# Kingst51.net
KiCad netlist of a schematic drawn in Altium Designer
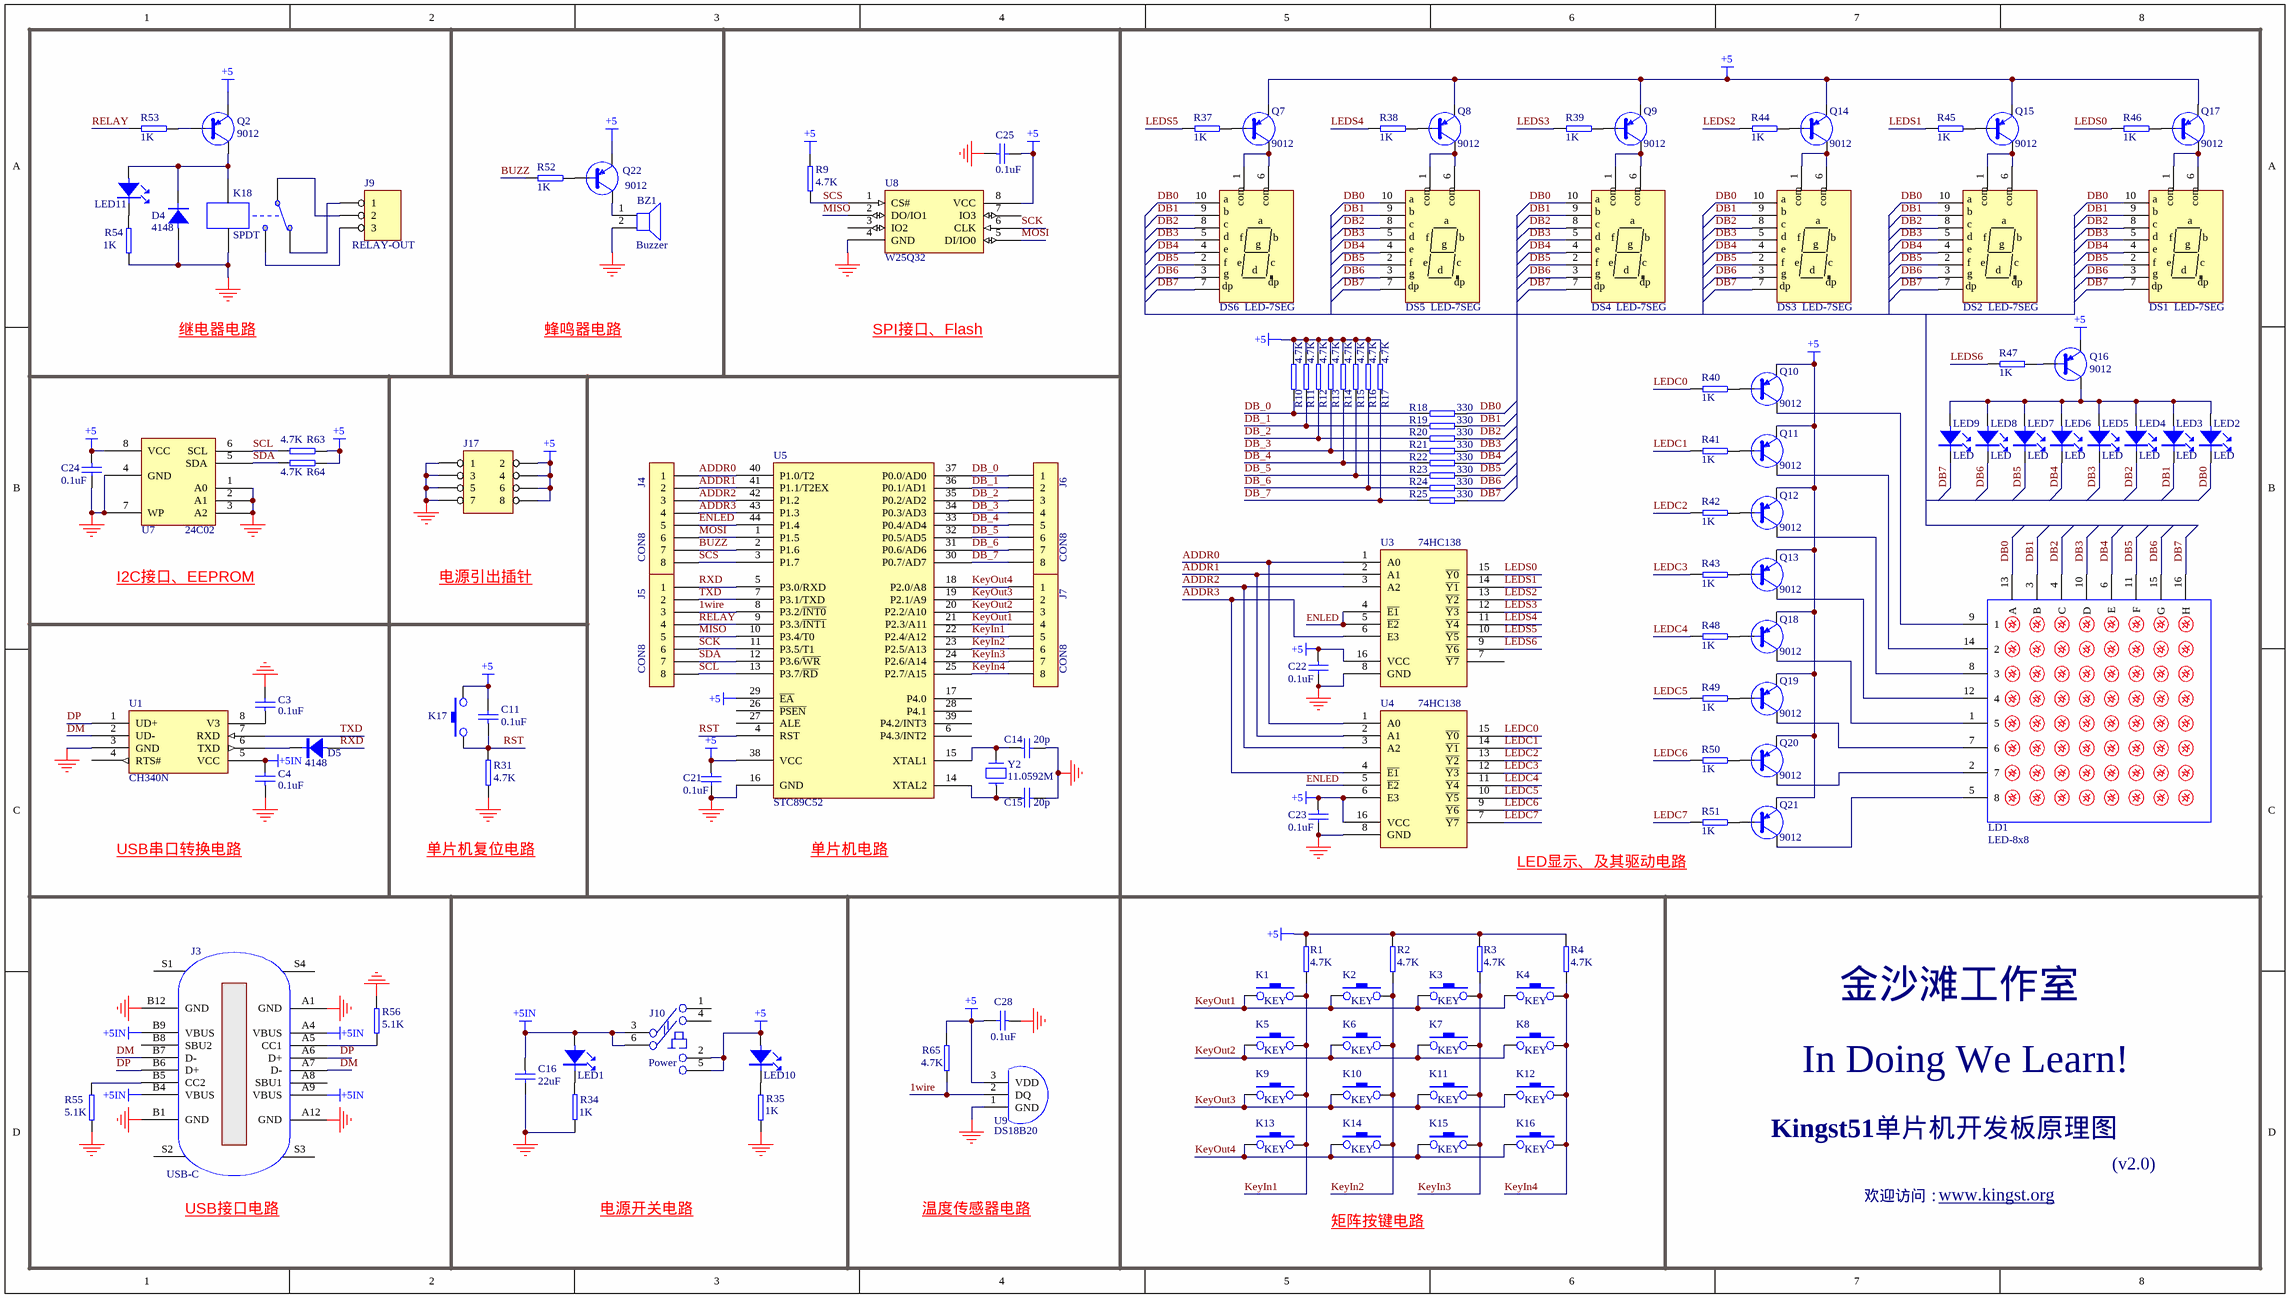
[diagram p0: Kingst51开发板原理图.SchDoc]

(export (version "E")
  (design (tool "Eeschema 10.0.6"))
  (components
    (comp (ref "BZ1") (value "Buzzer") (footprint "BUZZ-D12") (libsource (lib "*") (part "SPEAKER")))
    (comp (ref "C3") (value "0.1uF") (footprint "0603C") (libsource (lib "*") (part "CAP")))
    (comp (ref "C4") (value "0.1uF") (footprint "0603C") (libsource (lib "*") (part "CAP")))
    (comp (ref "C11") (value "0.1uF") (footprint "0603C") (libsource (lib "*") (part "CAP")))
    (comp (ref "C14") (value "20p") (footprint "0603C") (libsource (lib "*") (part "CAP")))
    (comp (ref "C15") (value "20p") (footprint "0603C") (libsource (lib "*") (part "CAP")))
    (comp (ref "C16") (value "22uF") (footprint "0805C") (libsource (lib "*") (part "CAP")))
    (comp (ref "C21") (value "0.1uF") (footprint "0603C") (libsource (lib "*") (part "CAP")))
    (comp (ref "C22") (value "0.1uF") (footprint "0603C") (libsource (lib "*") (part "CAP")))
    (comp (ref "C23") (value "0.1uF") (footprint "0603C") (libsource (lib "*") (part "CAP")))
    (comp (ref "C24") (value "0.1uF") (footprint "0603C") (libsource (lib "*") (part "CAP")))
    (comp (ref "C25") (value "0.1uF") (footprint "0603C") (libsource (lib "*") (part "CAP")))
    (comp (ref "C28") (value "0.1uF") (footprint "0603C") (libsource (lib "*") (part "CAP")))
    (comp (ref "D4")
      (value "4148")
      (footprint "SOD-123")
      (description "DIODE")
      (libsource (lib "schOthers") (part "DIODE"))
    )
    (comp (ref "D5")
      (value "4148")
      (footprint "SOD-123")
      (description "DIODE")
      (libsource (lib "schOthers") (part "DIODE"))
    )
    (comp (ref "DS1")
      (value "LED-7SEG")
      (footprint "LED-C7")
      (description "Seven-Segment Display, Right Hand Decimal")
      (libsource (lib "*") (part "LED-7SEG"))
    )
    (comp (ref "DS2")
      (value "LED-7SEG")
      (footprint "LED-C7")
      (description "Seven-Segment Display, Right Hand Decimal")
      (libsource (lib "*") (part "LED-7SEG"))
    )
    (comp (ref "DS3")
      (value "LED-7SEG")
      (footprint "LED-C7")
      (description "Seven-Segment Display, Right Hand Decimal")
      (libsource (lib "*") (part "LED-7SEG"))
    )
    (comp (ref "DS4")
      (value "LED-7SEG")
      (footprint "LED-C7")
      (description "Seven-Segment Display, Right Hand Decimal")
      (libsource (lib "*") (part "LED-7SEG"))
    )
    (comp (ref "DS5")
      (value "LED-7SEG")
      (footprint "LED-C7")
      (description "Seven-Segment Display, Right Hand Decimal")
      (libsource (lib "*") (part "LED-7SEG"))
    )
    (comp (ref "DS6")
      (value "LED-7SEG")
      (footprint "LED-C7")
      (description "Seven-Segment Display, Right Hand Decimal")
      (libsource (lib "*") (part "LED-7SEG"))
    )
    (comp (ref "J3")
      (value "USB-C")
      (footprint "USB-C-16P")
      (description "USB Type-C 16P 型插座")
      (libsource (lib "schOthers") (part "USB-C-16P"))
    )
    (comp (ref "J4")
      (value "CON8")
      (footprint "SIP8")
      (description "Connector")
      (libsource (lib "") (part "CON8_1"))
    )
    (comp (ref "J5")
      (value "CON8")
      (footprint "SIP8")
      (description "Connector")
      (libsource (lib "") (part "CON8_1"))
    )
    (comp (ref "J6")
      (value "CON8")
      (footprint "SIP8")
      (description "Connector")
      (libsource (lib "*") (part "CON8"))
    )
    (comp (ref "J7")
      (value "CON8")
      (footprint "SIP8")
      (description "Connector")
      (libsource (lib "*") (part "CON8"))
    )
    (comp (ref "J9")
      (value "RELAY-OUT")
      (footprint "P5.08-3P")
      (description "Connector 3p")
      (libsource (lib "schOthers") (part "CON3"))
    )
    (comp (ref "J10")
      (value "Power")
      (description "Self-locking button")
      (libsource (lib "schOthers") (part "KEY-SL"))
    )
    (comp (ref "J17")
      (value "CON4X2")
      (footprint "IDC4X2-M")
      (description "Connector 4*2p")
      (libsource (lib "schOthers") (part "CON4X2"))
    )
    (comp (ref "K1") (value "KEY") (footprint "KEY-6X6") (libsource (lib "*") (part "KEY")))
    (comp (ref "K2") (value "KEY") (footprint "KEY-6X6") (libsource (lib "*") (part "KEY")))
    (comp (ref "K3") (value "KEY") (footprint "KEY-6X6") (libsource (lib "*") (part "KEY")))
    (comp (ref "K4") (value "KEY") (footprint "KEY-6X6") (libsource (lib "*") (part "KEY")))
    (comp (ref "K5") (value "KEY") (footprint "KEY-6X6") (libsource (lib "*") (part "KEY")))
    (comp (ref "K6") (value "KEY") (footprint "KEY-6X6") (libsource (lib "*") (part "KEY")))
    (comp (ref "K7") (value "KEY") (footprint "KEY-6X6") (libsource (lib "*") (part "KEY")))
    (comp (ref "K8") (value "KEY") (footprint "KEY-6X6") (libsource (lib "*") (part "KEY")))
    (comp (ref "K9") (value "KEY") (footprint "KEY-6X6") (libsource (lib "*") (part "KEY")))
    (comp (ref "K10") (value "KEY") (footprint "KEY-6X6") (libsource (lib "*") (part "KEY")))
    (comp (ref "K11") (value "KEY") (footprint "KEY-6X6") (libsource (lib "*") (part "KEY")))
    (comp (ref "K12") (value "KEY") (footprint "KEY-6X6") (libsource (lib "*") (part "KEY")))
    (comp (ref "K13") (value "KEY") (footprint "KEY-6X6") (libsource (lib "*") (part "KEY")))
    (comp (ref "K14") (value "KEY") (footprint "KEY-6X6") (libsource (lib "*") (part "KEY")))
    (comp (ref "K15") (value "KEY") (footprint "KEY-6X6") (libsource (lib "*") (part "KEY")))
    (comp (ref "K16") (value "KEY") (footprint "KEY-6X6") (libsource (lib "*") (part "KEY")))
    (comp (ref "K17") (value "RESET") (footprint "KEY-6X6") (libsource (lib "*") (part "KEY")))
    (comp (ref "K18")
      (value "SPDT")
      (footprint "RELAY-SPDT")
      (libsource (lib "schOthers") (part "RELAY-SPDT"))
    )
    (comp (ref "LD1") (value "LED-8x8") (footprint "LED-8*8") (libsource (lib "*") (part "LED-8*8")))
    (comp (ref "LED1") (value "LED") (footprint "0805LD") (libsource (lib "*") (part "LED")))
    (comp (ref "LED2") (value "LED") (footprint "0805LD") (libsource (lib "*") (part "LED")))
    (comp (ref "LED3") (value "LED") (footprint "0805LD") (libsource (lib "*") (part "LED")))
    (comp (ref "LED4") (value "LED") (footprint "0805LD") (libsource (lib "*") (part "LED")))
    (comp (ref "LED5") (value "LED") (footprint "0805LD") (libsource (lib "*") (part "LED")))
    (comp (ref "LED6") (value "LED") (footprint "0805LD") (libsource (lib "*") (part "LED")))
    (comp (ref "LED7") (value "LED") (footprint "0805LD") (libsource (lib "*") (part "LED")))
    (comp (ref "LED8") (value "LED") (footprint "0805LD") (libsource (lib "*") (part "LED")))
    (comp (ref "LED9") (value "LED") (footprint "0805LD") (libsource (lib "*") (part "LED")))
    (comp (ref "LED10") (value "LED") (footprint "0805LD") (libsource (lib "*") (part "LED")))
    (comp (ref "LED11") (value "LED") (footprint "0805LD") (libsource (lib "*") (part "LED")))
    (comp (ref "Q2") (value "9012") (footprint "SOT-23-Q") (libsource (lib "*") (part "2N-PNP")))
    (comp (ref "Q7") (value "9012") (footprint "SOT-23-Q") (libsource (lib "*") (part "2N-PNP")))
    (comp (ref "Q8") (value "9012") (footprint "SOT-23-Q") (libsource (lib "*") (part "2N-PNP")))
    (comp (ref "Q9") (value "9012") (footprint "SOT-23-Q") (libsource (lib "*") (part "2N-PNP")))
    (comp (ref "Q10") (value "9012") (footprint "SOT-23-Q") (libsource (lib "*") (part "2N-PNP")))
    (comp (ref "Q11") (value "9012") (footprint "SOT-23-Q") (libsource (lib "*") (part "2N-PNP")))
    (comp (ref "Q12") (value "9012") (footprint "SOT-23-Q") (libsource (lib "*") (part "2N-PNP")))
    (comp (ref "Q13") (value "9012") (footprint "SOT-23-Q") (libsource (lib "*") (part "2N-PNP")))
    (comp (ref "Q14") (value "9012") (footprint "SOT-23-Q") (libsource (lib "*") (part "2N-PNP")))
    (comp (ref "Q15") (value "9012") (footprint "SOT-23-Q") (libsource (lib "*") (part "2N-PNP")))
    (comp (ref "Q16") (value "9012") (footprint "SOT-23-Q") (libsource (lib "*") (part "2N-PNP")))
    (comp (ref "Q17") (value "9012") (footprint "SOT-23-Q") (libsource (lib "*") (part "2N-PNP")))
    (comp (ref "Q18") (value "9012") (footprint "SOT-23-Q") (libsource (lib "*") (part "2N-PNP")))
    (comp (ref "Q19") (value "9012") (footprint "SOT-23-Q") (libsource (lib "*") (part "2N-PNP")))
    (comp (ref "Q20") (value "9012") (footprint "SOT-23-Q") (libsource (lib "*") (part "2N-PNP")))
    (comp (ref "Q21") (value "9012") (footprint "SOT-23-Q") (libsource (lib "*") (part "2N-PNP")))
    (comp (ref "Q22") (value "9012") (footprint "SOT-23-Q") (libsource (lib "*") (part "2N-PNP")))
    (comp (ref "R1") (value "4.7K") (footprint "0603R") (libsource (lib "*") (part "RES2")))
    (comp (ref "R2") (value "4.7K") (footprint "0603R") (libsource (lib "*") (part "RES2")))
    (comp (ref "R3") (value "4.7K") (footprint "0603R") (libsource (lib "*") (part "RES2")))
    (comp (ref "R4") (value "4.7K") (footprint "0603R") (libsource (lib "*") (part "RES2")))
    (comp (ref "R9") (value "4.7K") (footprint "0603R") (libsource (lib "*") (part "RES2")))
    (comp (ref "R10") (value "4.7K") (footprint "0603R") (libsource (lib "*") (part "RES2")))
    (comp (ref "R11") (value "4.7K") (footprint "0603R") (libsource (lib "*") (part "RES2")))
    (comp (ref "R12") (value "4.7K") (footprint "0603R") (libsource (lib "*") (part "RES2")))
    (comp (ref "R13") (value "4.7K") (footprint "0603R") (libsource (lib "*") (part "RES2")))
    (comp (ref "R14") (value "4.7K") (footprint "0603R") (libsource (lib "*") (part "RES2")))
    (comp (ref "R15") (value "4.7K") (footprint "0603R") (libsource (lib "*") (part "RES2")))
    (comp (ref "R16") (value "4.7K") (footprint "0603R") (libsource (lib "*") (part "RES2")))
    (comp (ref "R17") (value "4.7K") (footprint "0603R") (libsource (lib "*") (part "RES2")))
    (comp (ref "R18") (value "330") (footprint "0603R") (libsource (lib "*") (part "RES2")))
    (comp (ref "R19") (value "330") (footprint "0603R") (libsource (lib "*") (part "RES2")))
    (comp (ref "R20") (value "330") (footprint "0603R") (libsource (lib "*") (part "RES2")))
    (comp (ref "R21") (value "330") (footprint "0603R") (libsource (lib "*") (part "RES2")))
    (comp (ref "R22") (value "330") (footprint "0603R") (libsource (lib "*") (part "RES2")))
    (comp (ref "R23") (value "330") (footprint "0603R") (libsource (lib "*") (part "RES2")))
    (comp (ref "R24") (value "330") (footprint "0603R") (libsource (lib "*") (part "RES2")))
    (comp (ref "R25") (value "330") (footprint "0603R") (libsource (lib "*") (part "RES2")))
    (comp (ref "R31") (value "4.7K") (footprint "0603R") (libsource (lib "*") (part "RES2")))
    (comp (ref "R34") (value "1K") (footprint "0603R") (libsource (lib "*") (part "RES2")))
    (comp (ref "R35") (value "1K") (footprint "0603R") (libsource (lib "*") (part "RES2")))
    (comp (ref "R37") (value "1K") (footprint "0603R") (libsource (lib "*") (part "RES2")))
    (comp (ref "R38") (value "1K") (footprint "0603R") (libsource (lib "*") (part "RES2")))
    (comp (ref "R39") (value "1K") (footprint "0603R") (libsource (lib "*") (part "RES2")))
    (comp (ref "R40") (value "1K") (footprint "0603R") (libsource (lib "*") (part "RES2")))
    (comp (ref "R41") (value "1K") (footprint "0603R") (libsource (lib "*") (part "RES2")))
    (comp (ref "R42") (value "1K") (footprint "0603R") (libsource (lib "*") (part "RES2")))
    (comp (ref "R43") (value "1K") (footprint "0603R") (libsource (lib "*") (part "RES2")))
    (comp (ref "R44") (value "1K") (footprint "0603R") (libsource (lib "*") (part "RES2")))
    (comp (ref "R45") (value "1K") (footprint "0603R") (libsource (lib "*") (part "RES2")))
    (comp (ref "R46") (value "1K") (footprint "0603R") (libsource (lib "*") (part "RES2")))
    (comp (ref "R47") (value "1K") (footprint "0603R") (libsource (lib "*") (part "RES2")))
    (comp (ref "R48") (value "1K") (footprint "0603R") (libsource (lib "*") (part "RES2")))
    (comp (ref "R49") (value "1K") (footprint "0603R") (libsource (lib "*") (part "RES2")))
    (comp (ref "R50") (value "1K") (footprint "0603R") (libsource (lib "*") (part "RES2")))
    (comp (ref "R51") (value "1K") (footprint "0603R") (libsource (lib "*") (part "RES2")))
    (comp (ref "R52") (value "1K") (footprint "0603R") (libsource (lib "*") (part "RES2")))
    (comp (ref "R53") (value "1K") (footprint "0603R") (libsource (lib "*") (part "RES2")))
    (comp (ref "R54") (value "1K") (footprint "0603R") (libsource (lib "*") (part "RES2")))
    (comp (ref "R55") (value "5.1K") (footprint "0603R") (libsource (lib "*") (part "RES2")))
    (comp (ref "R56") (value "5.1K") (footprint "0603R") (libsource (lib "*") (part "RES2")))
    (comp (ref "R63") (value "4.7K") (footprint "0603R") (libsource (lib "*") (part "RES2")))
    (comp (ref "R64") (value "4.7K") (footprint "0603R") (libsource (lib "*") (part "RES2")))
    (comp (ref "R65") (value "4.7K") (footprint "0603R") (libsource (lib "*") (part "RES2")))
    (comp (ref "U1")
      (value "CH340N")
      (footprint "SOP-8_3.9")
      (description "USB to UART Bridge Controller")
      (libsource (lib "schChips") (part "CH340N"))
    )
    (comp (ref "U3") (value "74HC138") (footprint "SOP-16_3.9") (libsource (lib "*") (part "74XX138")))
    (comp (ref "U4") (value "74HC138") (footprint "SOP-16_3.9") (libsource (lib "*") (part "74XX138")))
    (comp (ref "U5")
      (value "STC89C52")
      (footprint "LQFP44_0.8")
      (description "STC89C52 LQFP44")
      (libsource (lib "schProcessor") (part "STC89C52-44P"))
    )
    (comp (ref "U7") (value "24C02") (footprint "SOP-8_3.9") (libsource (lib "*") (part "24C01")))
    (comp (ref "U8")
      (value "W25Q32")
      (footprint "SOP-8_5.3")
      (description "SPI Serial Flash")
      (libsource (lib "schChips") (part "W25Q128"))
    )
    (comp (ref "U9") (value "DS18B20") (footprint "TO-92") (libsource (lib "*") (part "DS18B20")))
    (comp (ref "Y2")
      (value "11.0592M")
      (footprint "SMD-3225-4P")
      (description "Crystal")
      (libsource (lib "schOthers") (part "CRYSTAL"))
    )
  )
  (nets
    (net (code "1") (name "+5") (class "Default")
      (node (ref "C11") (pin "2") (pinfunction "2_2") (pintype "passive"))
      (node (ref "C21") (pin "1") (pinfunction "1_1") (pintype "passive"))
      (node (ref "C22") (pin "1") (pinfunction "1_1") (pintype "passive"))
      (node (ref "C23") (pin "1") (pinfunction "1_1") (pintype "passive"))
      (node (ref "C24") (pin "1") (pinfunction "1_1") (pintype "passive"))
      (node (ref "C25") (pin "2") (pinfunction "2_2") (pintype "passive"))
      (node (ref "C28") (pin "2") (pinfunction "2_2") (pintype "passive"))
      (node (ref "J10") (pin "2") (pinfunction "2_2") (pintype "passive"))
      (node (ref "J10") (pin "5") (pinfunction "5_5") (pintype "passive"))
      (node (ref "J17") (pin "2") (pinfunction "2_2") (pintype "passive"))
      (node (ref "J17") (pin "4") (pinfunction "4_4") (pintype "passive"))
      (node (ref "J17") (pin "6") (pinfunction "6_6") (pintype "passive"))
      (node (ref "J17") (pin "8") (pinfunction "8_8") (pintype "passive"))
      (node (ref "K17") (pin "2") (pinfunction "2_2") (pintype "passive"))
      (node (ref "LED10") (pin "A") (pinfunction "1_A") (pintype "passive"))
      (node (ref "Q10") (pin "E") (pinfunction "E_E") (pintype "passive"))
      (node (ref "Q11") (pin "E") (pinfunction "E_E") (pintype "passive"))
      (node (ref "Q12") (pin "E") (pinfunction "E_E") (pintype "passive"))
      (node (ref "Q13") (pin "E") (pinfunction "E_E") (pintype "passive"))
      (node (ref "Q14") (pin "E") (pinfunction "E_E") (pintype "passive"))
      (node (ref "Q15") (pin "E") (pinfunction "E_E") (pintype "passive"))
      (node (ref "Q16") (pin "E") (pinfunction "E_E") (pintype "passive"))
      (node (ref "Q17") (pin "E") (pinfunction "E_E") (pintype "passive"))
      (node (ref "Q18") (pin "E") (pinfunction "E_E") (pintype "passive"))
      (node (ref "Q19") (pin "E") (pinfunction "E_E") (pintype "passive"))
      (node (ref "Q2") (pin "E") (pinfunction "E_E") (pintype "passive"))
      (node (ref "Q20") (pin "E") (pinfunction "E_E") (pintype "passive"))
      (node (ref "Q21") (pin "E") (pinfunction "E_E") (pintype "passive"))
      (node (ref "Q22") (pin "E") (pinfunction "E_E") (pintype "passive"))
      (node (ref "Q7") (pin "E") (pinfunction "E_E") (pintype "passive"))
      (node (ref "Q8") (pin "E") (pinfunction "E_E") (pintype "passive"))
      (node (ref "Q9") (pin "E") (pinfunction "E_E") (pintype "passive"))
      (node (ref "R1") (pin "2") (pinfunction "2_2") (pintype "passive"))
      (node (ref "R10") (pin "2") (pinfunction "2_2") (pintype "passive"))
      (node (ref "R11") (pin "2") (pinfunction "2_2") (pintype "passive"))
      (node (ref "R12") (pin "2") (pinfunction "2_2") (pintype "passive"))
      (node (ref "R13") (pin "2") (pinfunction "2_2") (pintype "passive"))
      (node (ref "R14") (pin "2") (pinfunction "2_2") (pintype "passive"))
      (node (ref "R15") (pin "2") (pinfunction "2_2") (pintype "passive"))
      (node (ref "R16") (pin "2") (pinfunction "2_2") (pintype "passive"))
      (node (ref "R17") (pin "2") (pinfunction "2_2") (pintype "passive"))
      (node (ref "R2") (pin "2") (pinfunction "2_2") (pintype "passive"))
      (node (ref "R3") (pin "2") (pinfunction "2_2") (pintype "passive"))
      (node (ref "R4") (pin "2") (pinfunction "2_2") (pintype "passive"))
      (node (ref "R63") (pin "2") (pinfunction "2_2") (pintype "passive"))
      (node (ref "R64") (pin "2") (pinfunction "2_2") (pintype "passive"))
      (node (ref "R65") (pin "2") (pinfunction "2_2") (pintype "passive"))
      (node (ref "R9") (pin "2") (pinfunction "2_2") (pintype "passive"))
      (node (ref "U3") (pin "16") (pinfunction "VCC_16") (pintype "passive"))
      (node (ref "U4") (pin "16") (pinfunction "VCC_16") (pintype "passive"))
      (node (ref "U4") (pin "6") (pinfunction "E3_6") (pintype "passive"))
      (node (ref "U5") (pin "29") (pinfunction "~{EA}_29") (pintype "passive"))
      (node (ref "U5") (pin "38") (pinfunction "VCC_38") (pintype "passive"))
      (node (ref "U7") (pin "8") (pinfunction "VCC_8") (pintype "passive"))
      (node (ref "U8") (pin "8") (pinfunction "VCC_8") (pintype "power_in"))
      (node (ref "U9") (pin "3") (pinfunction "VDD_3") (pintype "passive"))
    )
    (net (code "2") (name "+5IN") (class "Default")
      (node (ref "C16") (pin "1") (pinfunction "1_1") (pintype "passive"))
      (node (ref "C4") (pin "2") (pinfunction "2_2") (pintype "passive"))
      (node (ref "J10") (pin "3") (pinfunction "3_3") (pintype "passive"))
      (node (ref "J10") (pin "6") (pinfunction "6_6") (pintype "passive"))
      (node (ref "J3") (pin "A4") (pinfunction "VBUS_A4") (pintype "passive"))
      (node (ref "J3") (pin "A9") (pinfunction "VBUS_A9") (pintype "passive"))
      (node (ref "J3") (pin "B4") (pinfunction "VBUS_B4") (pintype "passive"))
      (node (ref "J3") (pin "B9") (pinfunction "VBUS_B9") (pintype "passive"))
      (node (ref "LED1") (pin "A") (pinfunction "1_A") (pintype "passive"))
      (node (ref "U1") (pin "5") (pinfunction "VCC_5") (pintype "passive"))
    )
    (net (code "3") (name "/1wire") (class "Default")
      (node (ref "J5") (pin "3") (pinfunction "3_3") (pintype "passive"))
      (node (ref "R65") (pin "1") (pinfunction "1_1") (pintype "passive"))
      (node (ref "U5") (pin "8") (pinfunction "P3.2/~{INT0}_8") (pintype "passive"))
      (node (ref "U9") (pin "2") (pinfunction "DQ_2") (pintype "passive"))
    )
    (net (code "4") (name "/ADDR0") (class "Default")
      (node (ref "J4") (pin "1") (pinfunction "1_1") (pintype "passive"))
      (node (ref "U3") (pin "1") (pinfunction "A0_1") (pintype "passive"))
      (node (ref "U4") (pin "1") (pinfunction "A0_1") (pintype "passive"))
      (node (ref "U5") (pin "40") (pinfunction "P1.0/T2_40") (pintype "passive"))
    )
    (net (code "5") (name "/ADDR1") (class "Default")
      (node (ref "J4") (pin "2") (pinfunction "2_2") (pintype "passive"))
      (node (ref "U3") (pin "2") (pinfunction "A1_2") (pintype "passive"))
      (node (ref "U4") (pin "2") (pinfunction "A1_2") (pintype "passive"))
      (node (ref "U5") (pin "41") (pinfunction "P1.1/T2EX_41") (pintype "passive"))
    )
    (net (code "6") (name "/ADDR2") (class "Default")
      (node (ref "J4") (pin "3") (pinfunction "3_3") (pintype "passive"))
      (node (ref "U3") (pin "3") (pinfunction "A2_3") (pintype "passive"))
      (node (ref "U4") (pin "3") (pinfunction "A2_3") (pintype "passive"))
      (node (ref "U5") (pin "42") (pinfunction "P1.2_42") (pintype "passive"))
    )
    (net (code "7") (name "/ADDR3") (class "Default")
      (node (ref "J4") (pin "4") (pinfunction "4_4") (pintype "passive"))
      (node (ref "U3") (pin "6") (pinfunction "E3_6") (pintype "passive"))
      (node (ref "U4") (pin "4") (pinfunction "~{E1}_4") (pintype "passive"))
      (node (ref "U5") (pin "43") (pinfunction "P1.3_43") (pintype "passive"))
    )
    (net (code "8") (name "/BUZZ") (class "Default")
      (node (ref "J4") (pin "7") (pinfunction "7_7") (pintype "passive"))
      (node (ref "R52") (pin "1") (pinfunction "1_1") (pintype "passive"))
      (node (ref "U5") (pin "2") (pinfunction "P1.6_2") (pintype "passive"))
    )
    (net (code "9") (name "/DB0") (class "Default")
      (node (ref "DS1") (pin "10") (pinfunction "a_10") (pintype "passive"))
      (node (ref "DS2") (pin "10") (pinfunction "a_10") (pintype "passive"))
      (node (ref "DS3") (pin "10") (pinfunction "a_10") (pintype "passive"))
      (node (ref "DS4") (pin "10") (pinfunction "a_10") (pintype "passive"))
      (node (ref "DS5") (pin "10") (pinfunction "a_10") (pintype "passive"))
      (node (ref "DS6") (pin "10") (pinfunction "a_10") (pintype "passive"))
      (node (ref "LD1") (pin "13") (pinfunction "A_13") (pintype "passive"))
      (node (ref "LED2") (pin "K") (pinfunction "2_K") (pintype "passive"))
      (node (ref "R18") (pin "1") (pinfunction "1_1") (pintype "passive"))
    )
    (net (code "10") (name "/DB1") (class "Default")
      (node (ref "DS1") (pin "9") (pinfunction "b_9") (pintype "passive"))
      (node (ref "DS2") (pin "9") (pinfunction "b_9") (pintype "passive"))
      (node (ref "DS3") (pin "9") (pinfunction "b_9") (pintype "passive"))
      (node (ref "DS4") (pin "9") (pinfunction "b_9") (pintype "passive"))
      (node (ref "DS5") (pin "9") (pinfunction "b_9") (pintype "passive"))
      (node (ref "DS6") (pin "9") (pinfunction "b_9") (pintype "passive"))
      (node (ref "LD1") (pin "3") (pinfunction "B_3") (pintype "passive"))
      (node (ref "LED3") (pin "K") (pinfunction "2_K") (pintype "passive"))
      (node (ref "R19") (pin "1") (pinfunction "1_1") (pintype "passive"))
    )
    (net (code "11") (name "/DB2") (class "Default")
      (node (ref "DS1") (pin "8") (pinfunction "c_8") (pintype "passive"))
      (node (ref "DS2") (pin "8") (pinfunction "c_8") (pintype "passive"))
      (node (ref "DS3") (pin "8") (pinfunction "c_8") (pintype "passive"))
      (node (ref "DS4") (pin "8") (pinfunction "c_8") (pintype "passive"))
      (node (ref "DS5") (pin "8") (pinfunction "c_8") (pintype "passive"))
      (node (ref "DS6") (pin "8") (pinfunction "c_8") (pintype "passive"))
      (node (ref "LD1") (pin "4") (pinfunction "C_4") (pintype "passive"))
      (node (ref "LED4") (pin "K") (pinfunction "2_K") (pintype "passive"))
      (node (ref "R20") (pin "1") (pinfunction "1_1") (pintype "passive"))
    )
    (net (code "12") (name "/DB3") (class "Default")
      (node (ref "DS1") (pin "5") (pinfunction "d_5") (pintype "passive"))
      (node (ref "DS2") (pin "5") (pinfunction "d_5") (pintype "passive"))
      (node (ref "DS3") (pin "5") (pinfunction "d_5") (pintype "passive"))
      (node (ref "DS4") (pin "5") (pinfunction "d_5") (pintype "passive"))
      (node (ref "DS5") (pin "5") (pinfunction "d_5") (pintype "passive"))
      (node (ref "DS6") (pin "5") (pinfunction "d_5") (pintype "passive"))
      (node (ref "LD1") (pin "10") (pinfunction "D_10") (pintype "passive"))
      (node (ref "LED5") (pin "K") (pinfunction "2_K") (pintype "passive"))
      (node (ref "R21") (pin "1") (pinfunction "1_1") (pintype "passive"))
    )
    (net (code "13") (name "/DB4") (class "Default")
      (node (ref "DS1") (pin "4") (pinfunction "e_4") (pintype "passive"))
      (node (ref "DS2") (pin "4") (pinfunction "e_4") (pintype "passive"))
      (node (ref "DS3") (pin "4") (pinfunction "e_4") (pintype "passive"))
      (node (ref "DS4") (pin "4") (pinfunction "e_4") (pintype "passive"))
      (node (ref "DS5") (pin "4") (pinfunction "e_4") (pintype "passive"))
      (node (ref "DS6") (pin "4") (pinfunction "e_4") (pintype "passive"))
      (node (ref "LD1") (pin "6") (pinfunction "E_6") (pintype "passive"))
      (node (ref "LED6") (pin "K") (pinfunction "2_K") (pintype "passive"))
      (node (ref "R22") (pin "1") (pinfunction "1_1") (pintype "passive"))
    )
    (net (code "14") (name "/DB5") (class "Default")
      (node (ref "DS1") (pin "2") (pinfunction "f_2") (pintype "passive"))
      (node (ref "DS2") (pin "2") (pinfunction "f_2") (pintype "passive"))
      (node (ref "DS3") (pin "2") (pinfunction "f_2") (pintype "passive"))
      (node (ref "DS4") (pin "2") (pinfunction "f_2") (pintype "passive"))
      (node (ref "DS5") (pin "2") (pinfunction "f_2") (pintype "passive"))
      (node (ref "DS6") (pin "2") (pinfunction "f_2") (pintype "passive"))
      (node (ref "LD1") (pin "11") (pinfunction "F_11") (pintype "passive"))
      (node (ref "LED7") (pin "K") (pinfunction "2_K") (pintype "passive"))
      (node (ref "R23") (pin "1") (pinfunction "1_1") (pintype "passive"))
    )
    (net (code "15") (name "/DB6") (class "Default")
      (node (ref "DS1") (pin "3") (pinfunction "g_3") (pintype "passive"))
      (node (ref "DS2") (pin "3") (pinfunction "g_3") (pintype "passive"))
      (node (ref "DS3") (pin "3") (pinfunction "g_3") (pintype "passive"))
      (node (ref "DS4") (pin "3") (pinfunction "g_3") (pintype "passive"))
      (node (ref "DS5") (pin "3") (pinfunction "g_3") (pintype "passive"))
      (node (ref "DS6") (pin "3") (pinfunction "g_3") (pintype "passive"))
      (node (ref "LD1") (pin "15") (pinfunction "G_15") (pintype "passive"))
      (node (ref "LED8") (pin "K") (pinfunction "2_K") (pintype "passive"))
      (node (ref "R24") (pin "1") (pinfunction "1_1") (pintype "passive"))
    )
    (net (code "16") (name "/DB7") (class "Default")
      (node (ref "DS1") (pin "7") (pinfunction "dp_7") (pintype "passive"))
      (node (ref "DS2") (pin "7") (pinfunction "dp_7") (pintype "passive"))
      (node (ref "DS3") (pin "7") (pinfunction "dp_7") (pintype "passive"))
      (node (ref "DS4") (pin "7") (pinfunction "dp_7") (pintype "passive"))
      (node (ref "DS5") (pin "7") (pinfunction "dp_7") (pintype "passive"))
      (node (ref "DS6") (pin "7") (pinfunction "dp_7") (pintype "passive"))
      (node (ref "LD1") (pin "16") (pinfunction "H_16") (pintype "passive"))
      (node (ref "LED9") (pin "K") (pinfunction "2_K") (pintype "passive"))
      (node (ref "R25") (pin "1") (pinfunction "1_1") (pintype "passive"))
    )
    (net (code "17") (name "/DB_0") (class "Default")
      (node (ref "J6") (pin "1") (pinfunction "1_1") (pintype "passive"))
      (node (ref "R10") (pin "1") (pinfunction "1_1") (pintype "passive"))
      (node (ref "R18") (pin "2") (pinfunction "2_2") (pintype "passive"))
      (node (ref "U5") (pin "37") (pinfunction "P0.0/AD0_37") (pintype "passive"))
    )
    (net (code "18") (name "/DB_1") (class "Default")
      (node (ref "J6") (pin "2") (pinfunction "2_2") (pintype "passive"))
      (node (ref "R11") (pin "1") (pinfunction "1_1") (pintype "passive"))
      (node (ref "R19") (pin "2") (pinfunction "2_2") (pintype "passive"))
      (node (ref "U5") (pin "36") (pinfunction "P0.1/AD1_36") (pintype "passive"))
    )
    (net (code "19") (name "/DB_2") (class "Default")
      (node (ref "J6") (pin "3") (pinfunction "3_3") (pintype "passive"))
      (node (ref "R12") (pin "1") (pinfunction "1_1") (pintype "passive"))
      (node (ref "R20") (pin "2") (pinfunction "2_2") (pintype "passive"))
      (node (ref "U5") (pin "35") (pinfunction "P0.2/AD2_35") (pintype "passive"))
    )
    (net (code "20") (name "/DB_3") (class "Default")
      (node (ref "J6") (pin "4") (pinfunction "4_4") (pintype "passive"))
      (node (ref "R13") (pin "1") (pinfunction "1_1") (pintype "passive"))
      (node (ref "R21") (pin "2") (pinfunction "2_2") (pintype "passive"))
      (node (ref "U5") (pin "34") (pinfunction "P0.3/AD3_34") (pintype "passive"))
    )
    (net (code "21") (name "/DB_4") (class "Default")
      (node (ref "J6") (pin "5") (pinfunction "5_5") (pintype "passive"))
      (node (ref "R14") (pin "1") (pinfunction "1_1") (pintype "passive"))
      (node (ref "R22") (pin "2") (pinfunction "2_2") (pintype "passive"))
      (node (ref "U5") (pin "33") (pinfunction "P0.4/AD4_33") (pintype "passive"))
    )
    (net (code "22") (name "/DB_5") (class "Default")
      (node (ref "J6") (pin "6") (pinfunction "6_6") (pintype "passive"))
      (node (ref "R15") (pin "1") (pinfunction "1_1") (pintype "passive"))
      (node (ref "R23") (pin "2") (pinfunction "2_2") (pintype "passive"))
      (node (ref "U5") (pin "32") (pinfunction "P0.5/AD5_32") (pintype "passive"))
    )
    (net (code "23") (name "/DB_6") (class "Default")
      (node (ref "J6") (pin "7") (pinfunction "7_7") (pintype "passive"))
      (node (ref "R16") (pin "1") (pinfunction "1_1") (pintype "passive"))
      (node (ref "R24") (pin "2") (pinfunction "2_2") (pintype "passive"))
      (node (ref "U5") (pin "31") (pinfunction "P0.6/AD6_31") (pintype "passive"))
    )
    (net (code "24") (name "/DB_7") (class "Default")
      (node (ref "J6") (pin "8") (pinfunction "8_8") (pintype "passive"))
      (node (ref "R17") (pin "1") (pinfunction "1_1") (pintype "passive"))
      (node (ref "R25") (pin "2") (pinfunction "2_2") (pintype "passive"))
      (node (ref "U5") (pin "30") (pinfunction "P0.7/AD7_30") (pintype "passive"))
    )
    (net (code "25") (name "/DM") (class "Default")
      (node (ref "J3") (pin "A7") (pinfunction "D-_A7") (pintype "passive"))
      (node (ref "J3") (pin "B7") (pinfunction "D-_B7") (pintype "passive"))
      (node (ref "U1") (pin "2") (pinfunction "UD-_2") (pintype "passive"))
    )
    (net (code "26") (name "/DP") (class "Default")
      (node (ref "J3") (pin "A6") (pinfunction "D+_A6") (pintype "passive"))
      (node (ref "J3") (pin "B6") (pinfunction "D+_B6") (pintype "passive"))
      (node (ref "U1") (pin "1") (pinfunction "UD+_1") (pintype "passive"))
    )
    (net (code "27") (name "/ENLED") (class "Default")
      (node (ref "J4") (pin "5") (pinfunction "5_5") (pintype "passive"))
      (node (ref "U3") (pin "4") (pinfunction "~{E1}_4") (pintype "passive"))
      (node (ref "U3") (pin "5") (pinfunction "~{E2}_5") (pintype "passive"))
      (node (ref "U4") (pin "5") (pinfunction "~{E2}_5") (pintype "passive"))
      (node (ref "U5") (pin "44") (pinfunction "P1.4_44") (pintype "passive"))
    )
    (net (code "28") (name "/KeyIn1") (class "Default")
      (node (ref "J7") (pin "5") (pinfunction "5_5") (pintype "passive"))
      (node (ref "K1") (pin "1") (pinfunction "1_1") (pintype "passive"))
      (node (ref "K13") (pin "1") (pinfunction "1_1") (pintype "passive"))
      (node (ref "K5") (pin "1") (pinfunction "1_1") (pintype "passive"))
      (node (ref "K9") (pin "1") (pinfunction "1_1") (pintype "passive"))
      (node (ref "R1") (pin "1") (pinfunction "1_1") (pintype "passive"))
      (node (ref "U5") (pin "22") (pinfunction "P2.4/A12_22") (pintype "passive"))
    )
    (net (code "29") (name "/KeyIn2") (class "Default")
      (node (ref "J7") (pin "6") (pinfunction "6_6") (pintype "passive"))
      (node (ref "K10") (pin "1") (pinfunction "1_1") (pintype "passive"))
      (node (ref "K14") (pin "1") (pinfunction "1_1") (pintype "passive"))
      (node (ref "K2") (pin "1") (pinfunction "1_1") (pintype "passive"))
      (node (ref "K6") (pin "1") (pinfunction "1_1") (pintype "passive"))
      (node (ref "R2") (pin "1") (pinfunction "1_1") (pintype "passive"))
      (node (ref "U5") (pin "23") (pinfunction "P2.5/A13_23") (pintype "passive"))
    )
    (net (code "30") (name "/KeyIn3") (class "Default")
      (node (ref "J7") (pin "7") (pinfunction "7_7") (pintype "passive"))
      (node (ref "K11") (pin "1") (pinfunction "1_1") (pintype "passive"))
      (node (ref "K15") (pin "1") (pinfunction "1_1") (pintype "passive"))
      (node (ref "K3") (pin "1") (pinfunction "1_1") (pintype "passive"))
      (node (ref "K7") (pin "1") (pinfunction "1_1") (pintype "passive"))
      (node (ref "R3") (pin "1") (pinfunction "1_1") (pintype "passive"))
      (node (ref "U5") (pin "24") (pinfunction "P2.6/A14_24") (pintype "passive"))
    )
    (net (code "31") (name "/KeyIn4") (class "Default")
      (node (ref "J7") (pin "8") (pinfunction "8_8") (pintype "passive"))
      (node (ref "K12") (pin "1") (pinfunction "1_1") (pintype "passive"))
      (node (ref "K16") (pin "1") (pinfunction "1_1") (pintype "passive"))
      (node (ref "K4") (pin "1") (pinfunction "1_1") (pintype "passive"))
      (node (ref "K8") (pin "1") (pinfunction "1_1") (pintype "passive"))
      (node (ref "R4") (pin "1") (pinfunction "1_1") (pintype "passive"))
      (node (ref "U5") (pin "25") (pinfunction "P2.7/A15_25") (pintype "passive"))
    )
    (net (code "32") (name "/KeyOut1") (class "Default")
      (node (ref "J7") (pin "4") (pinfunction "4_4") (pintype "passive"))
      (node (ref "K1") (pin "2") (pinfunction "2_2") (pintype "passive"))
      (node (ref "K2") (pin "2") (pinfunction "2_2") (pintype "passive"))
      (node (ref "K3") (pin "2") (pinfunction "2_2") (pintype "passive"))
      (node (ref "K4") (pin "2") (pinfunction "2_2") (pintype "passive"))
      (node (ref "U5") (pin "21") (pinfunction "P2.3/A11_21") (pintype "passive"))
    )
    (net (code "33") (name "/KeyOut2") (class "Default")
      (node (ref "J7") (pin "3") (pinfunction "3_3") (pintype "passive"))
      (node (ref "K5") (pin "2") (pinfunction "2_2") (pintype "passive"))
      (node (ref "K6") (pin "2") (pinfunction "2_2") (pintype "passive"))
      (node (ref "K7") (pin "2") (pinfunction "2_2") (pintype "passive"))
      (node (ref "K8") (pin "2") (pinfunction "2_2") (pintype "passive"))
      (node (ref "U5") (pin "20") (pinfunction "P2.2/A10_20") (pintype "passive"))
    )
    (net (code "34") (name "/KeyOut3") (class "Default")
      (node (ref "J7") (pin "2") (pinfunction "2_2") (pintype "passive"))
      (node (ref "K10") (pin "2") (pinfunction "2_2") (pintype "passive"))
      (node (ref "K11") (pin "2") (pinfunction "2_2") (pintype "passive"))
      (node (ref "K12") (pin "2") (pinfunction "2_2") (pintype "passive"))
      (node (ref "K9") (pin "2") (pinfunction "2_2") (pintype "passive"))
      (node (ref "U5") (pin "19") (pinfunction "P2.1/A9_19") (pintype "passive"))
    )
    (net (code "35") (name "/KeyOut4") (class "Default")
      (node (ref "J7") (pin "1") (pinfunction "1_1") (pintype "passive"))
      (node (ref "K13") (pin "2") (pinfunction "2_2") (pintype "passive"))
      (node (ref "K14") (pin "2") (pinfunction "2_2") (pintype "passive"))
      (node (ref "K15") (pin "2") (pinfunction "2_2") (pintype "passive"))
      (node (ref "K16") (pin "2") (pinfunction "2_2") (pintype "passive"))
      (node (ref "U5") (pin "18") (pinfunction "P2.0/A8_18") (pintype "passive"))
    )
    (net (code "36") (name "/LEDC0") (class "Default")
      (node (ref "R40") (pin "1") (pinfunction "1_1") (pintype "passive"))
      (node (ref "U4") (pin "15") (pinfunction "~{Y0}_15") (pintype "passive"))
    )
    (net (code "37") (name "/LEDC1") (class "Default")
      (node (ref "R41") (pin "1") (pinfunction "1_1") (pintype "passive"))
      (node (ref "U4") (pin "14") (pinfunction "~{Y1}_14") (pintype "passive"))
    )
    (net (code "38") (name "/LEDC2") (class "Default")
      (node (ref "R42") (pin "1") (pinfunction "1_1") (pintype "passive"))
      (node (ref "U4") (pin "13") (pinfunction "~{Y2}_13") (pintype "passive"))
    )
    (net (code "39") (name "/LEDC3") (class "Default")
      (node (ref "R43") (pin "1") (pinfunction "1_1") (pintype "passive"))
      (node (ref "U4") (pin "12") (pinfunction "~{Y3}_12") (pintype "passive"))
    )
    (net (code "40") (name "/LEDC4") (class "Default")
      (node (ref "R48") (pin "1") (pinfunction "1_1") (pintype "passive"))
      (node (ref "U4") (pin "11") (pinfunction "~{Y4}_11") (pintype "passive"))
    )
    (net (code "41") (name "/LEDC5") (class "Default")
      (node (ref "R49") (pin "1") (pinfunction "1_1") (pintype "passive"))
      (node (ref "U4") (pin "10") (pinfunction "~{Y5}_10") (pintype "passive"))
    )
    (net (code "42") (name "/LEDC6") (class "Default")
      (node (ref "R50") (pin "1") (pinfunction "1_1") (pintype "passive"))
      (node (ref "U4") (pin "9") (pinfunction "~{Y6}_9") (pintype "passive"))
    )
    (net (code "43") (name "/LEDC7") (class "Default")
      (node (ref "R51") (pin "1") (pinfunction "1_1") (pintype "passive"))
      (node (ref "U4") (pin "7") (pinfunction "~{Y7}_7") (pintype "passive"))
    )
    (net (code "44") (name "/LEDS0") (class "Default")
      (node (ref "R46") (pin "1") (pinfunction "1_1") (pintype "passive"))
      (node (ref "U3") (pin "15") (pinfunction "~{Y0}_15") (pintype "passive"))
    )
    (net (code "45") (name "/LEDS1") (class "Default")
      (node (ref "R45") (pin "1") (pinfunction "1_1") (pintype "passive"))
      (node (ref "U3") (pin "14") (pinfunction "~{Y1}_14") (pintype "passive"))
    )
    (net (code "46") (name "/LEDS2") (class "Default")
      (node (ref "R44") (pin "1") (pinfunction "1_1") (pintype "passive"))
      (node (ref "U3") (pin "13") (pinfunction "~{Y2}_13") (pintype "passive"))
    )
    (net (code "47") (name "/LEDS3") (class "Default")
      (node (ref "R39") (pin "1") (pinfunction "1_1") (pintype "passive"))
      (node (ref "U3") (pin "12") (pinfunction "~{Y3}_12") (pintype "passive"))
    )
    (net (code "48") (name "/LEDS4") (class "Default")
      (node (ref "R38") (pin "1") (pinfunction "1_1") (pintype "passive"))
      (node (ref "U3") (pin "11") (pinfunction "~{Y4}_11") (pintype "passive"))
    )
    (net (code "49") (name "/LEDS5") (class "Default")
      (node (ref "R37") (pin "1") (pinfunction "1_1") (pintype "passive"))
      (node (ref "U3") (pin "10") (pinfunction "~{Y5}_10") (pintype "passive"))
    )
    (net (code "50") (name "/LEDS6") (class "Default")
      (node (ref "R47") (pin "2") (pinfunction "2_2") (pintype "passive"))
      (node (ref "U3") (pin "9") (pinfunction "~{Y6}_9") (pintype "passive"))
    )
    (net (code "51") (name "/MISO") (class "Default")
      (node (ref "J5") (pin "5") (pinfunction "5_5") (pintype "passive"))
      (node (ref "U5") (pin "10") (pinfunction "P3.4/T0_10") (pintype "passive"))
      (node (ref "U8") (pin "2") (pinfunction "DO/IO1_2") (pintype "bidirectional"))
    )
    (net (code "52") (name "/MOSI") (class "Default")
      (node (ref "J4") (pin "6") (pinfunction "6_6") (pintype "passive"))
      (node (ref "U5") (pin "1") (pinfunction "P1.5_1") (pintype "passive"))
      (node (ref "U8") (pin "5") (pinfunction "DI/IO0_5") (pintype "bidirectional"))
    )
    (net (code "53") (name "/RELAY") (class "Default")
      (node (ref "J5") (pin "4") (pinfunction "4_4") (pintype "passive"))
      (node (ref "R53") (pin "1") (pinfunction "1_1") (pintype "passive"))
      (node (ref "U5") (pin "9") (pinfunction "P3.3/~{INT1}_9") (pintype "passive"))
    )
    (net (code "54") (name "/RST") (class "Default")
      (node (ref "C11") (pin "1") (pinfunction "1_1") (pintype "passive"))
      (node (ref "K17") (pin "1") (pinfunction "1_1") (pintype "passive"))
      (node (ref "R31") (pin "1") (pinfunction "1_1") (pintype "passive"))
      (node (ref "U5") (pin "4") (pinfunction "RST_4") (pintype "passive"))
    )
    (net (code "55") (name "/RXD") (class "Default")
      (node (ref "D5") (pin "A") (pinfunction "1_A") (pintype "passive"))
      (node (ref "J5") (pin "1") (pinfunction "1_1") (pintype "passive"))
      (node (ref "U5") (pin "5") (pinfunction "P3.0/RXD_5") (pintype "passive"))
    )
    (net (code "56") (name "/SCK") (class "Default")
      (node (ref "J5") (pin "6") (pinfunction "6_6") (pintype "passive"))
      (node (ref "U5") (pin "11") (pinfunction "P3.5/T1_11") (pintype "passive"))
      (node (ref "U8") (pin "6") (pinfunction "CLK_6") (pintype "input"))
    )
    (net (code "57") (name "/SCL") (class "Default")
      (node (ref "J5") (pin "8") (pinfunction "8_8") (pintype "passive"))
      (node (ref "R63") (pin "1") (pinfunction "1_1") (pintype "passive"))
      (node (ref "U5") (pin "13") (pinfunction "P3.7/~{RD}_13") (pintype "passive"))
      (node (ref "U7") (pin "6") (pinfunction "SCL_6") (pintype "passive"))
    )
    (net (code "58") (name "/SCS") (class "Default")
      (node (ref "J4") (pin "8") (pinfunction "8_8") (pintype "passive"))
      (node (ref "R9") (pin "1") (pinfunction "1_1") (pintype "passive"))
      (node (ref "U5") (pin "3") (pinfunction "P1.7_3") (pintype "passive"))
      (node (ref "U8") (pin "1") (pinfunction "CS#_1") (pintype "input"))
    )
    (net (code "59") (name "/SDA") (class "Default")
      (node (ref "J5") (pin "7") (pinfunction "7_7") (pintype "passive"))
      (node (ref "R64") (pin "1") (pinfunction "1_1") (pintype "passive"))
      (node (ref "U5") (pin "12") (pinfunction "P3.6/~{WR}_12") (pintype "passive"))
      (node (ref "U7") (pin "5") (pinfunction "SDA_5") (pintype "passive"))
    )
    (net (code "60") (name "/TXD") (class "Default")
      (node (ref "J5") (pin "2") (pinfunction "2_2") (pintype "passive"))
      (node (ref "U1") (pin "7") (pinfunction "RXD_7") (pintype "input"))
      (node (ref "U5") (pin "7") (pinfunction "P3.1/TXD_7") (pintype "passive"))
    )
    (net (code "61") (name "GND") (class "Default")
      (node (ref "BZ1") (pin "2") (pinfunction "2_2") (pintype "passive"))
      (node (ref "C14") (pin "2") (pinfunction "2_2") (pintype "passive"))
      (node (ref "C15") (pin "2") (pinfunction "2_2") (pintype "passive"))
      (node (ref "C16") (pin "2") (pinfunction "2_2") (pintype "passive"))
      (node (ref "C21") (pin "2") (pinfunction "2_2") (pintype "passive"))
      (node (ref "C22") (pin "2") (pinfunction "2_2") (pintype "passive"))
      (node (ref "C23") (pin "2") (pinfunction "2_2") (pintype "passive"))
      (node (ref "C24") (pin "2") (pinfunction "2_2") (pintype "passive"))
      (node (ref "C25") (pin "1") (pinfunction "1_1") (pintype "passive"))
      (node (ref "C28") (pin "1") (pinfunction "1_1") (pintype "passive"))
      (node (ref "C3") (pin "2") (pinfunction "2_2") (pintype "passive"))
      (node (ref "C4") (pin "1") (pinfunction "1_1") (pintype "passive"))
      (node (ref "D4") (pin "A") (pinfunction "1_A") (pintype "passive"))
      (node (ref "J17") (pin "1") (pinfunction "1_1") (pintype "passive"))
      (node (ref "J17") (pin "3") (pinfunction "3_3") (pintype "passive"))
      (node (ref "J17") (pin "5") (pinfunction "5_5") (pintype "passive"))
      (node (ref "J17") (pin "7") (pinfunction "7_7") (pintype "passive"))
      (node (ref "J3") (pin "A1") (pinfunction "GND_A1") (pintype "passive"))
      (node (ref "J3") (pin "A12") (pinfunction "GND_A12") (pintype "passive"))
      (node (ref "J3") (pin "B1") (pinfunction "GND_B1") (pintype "passive"))
      (node (ref "J3") (pin "B12") (pinfunction "GND_B12") (pintype "passive"))
      (node (ref "K18") (pin "C2") (pinfunction "C2_C2") (pintype "passive"))
      (node (ref "R31") (pin "2") (pinfunction "2_2") (pintype "passive"))
      (node (ref "R34") (pin "2") (pinfunction "2_2") (pintype "passive"))
      (node (ref "R35") (pin "1") (pinfunction "1_1") (pintype "passive"))
      (node (ref "R54") (pin "1") (pinfunction "1_1") (pintype "passive"))
      (node (ref "R55") (pin "1") (pinfunction "1_1") (pintype "passive"))
      (node (ref "R56") (pin "2") (pinfunction "2_2") (pintype "passive"))
      (node (ref "U1") (pin "3") (pinfunction "GND_3") (pintype "passive"))
      (node (ref "U3") (pin "8") (pinfunction "GND_8") (pintype "passive"))
      (node (ref "U4") (pin "8") (pinfunction "GND_8") (pintype "passive"))
      (node (ref "U5") (pin "16") (pinfunction "GND_16") (pintype "passive"))
      (node (ref "U7") (pin "1") (pinfunction "A0_1") (pintype "passive"))
      (node (ref "U7") (pin "2") (pinfunction "A1_2") (pintype "passive"))
      (node (ref "U7") (pin "3") (pinfunction "A2_3") (pintype "passive"))
      (node (ref "U7") (pin "4") (pinfunction "GND_4") (pintype "passive"))
      (node (ref "U7") (pin "7") (pinfunction "WP_7") (pintype "passive"))
      (node (ref "U8") (pin "4") (pinfunction "GND_4") (pintype "power_in"))
      (node (ref "U9") (pin "1") (pinfunction "GND_1") (pintype "passive"))
    )
    (net (code "62") (name "Net-(BZ1-Pad1)") (class "Default")
      (node (ref "BZ1") (pin "1") (pinfunction "1_1") (pintype "passive"))
      (node (ref "Q22") (pin "C") (pinfunction "C_C") (pintype "passive"))
    )
    (net (code "63") (name "Net-(D4-2)") (class "Default")
      (node (ref "D4") (pin "K") (pinfunction "2_K") (pintype "passive"))
      (node (ref "K18") (pin "C1") (pinfunction "C1_C1") (pintype "passive"))
      (node (ref "LED11") (pin "A") (pinfunction "1_A") (pintype "passive"))
      (node (ref "Q2") (pin "C") (pinfunction "C_C") (pintype "passive"))
    )
    (net (code "64") (name "Net-(D5-2)") (class "Default")
      (node (ref "D5") (pin "K") (pinfunction "2_K") (pintype "passive"))
      (node (ref "U1") (pin "6") (pinfunction "TXD_6") (pintype "output"))
    )
    (net (code "65") (name "Net-(DS1-com-Pad1)") (class "Default")
      (node (ref "DS1") (pin "1") (pinfunction "com_1") (pintype "passive"))
      (node (ref "DS1") (pin "6") (pinfunction "com_6") (pintype "passive"))
      (node (ref "Q17") (pin "C") (pinfunction "C_C") (pintype "passive"))
    )
    (net (code "66") (name "Net-(DS2-com-Pad1)") (class "Default")
      (node (ref "DS2") (pin "1") (pinfunction "com_1") (pintype "passive"))
      (node (ref "DS2") (pin "6") (pinfunction "com_6") (pintype "passive"))
      (node (ref "Q15") (pin "C") (pinfunction "C_C") (pintype "passive"))
    )
    (net (code "67") (name "Net-(DS3-com-Pad1)") (class "Default")
      (node (ref "DS3") (pin "1") (pinfunction "com_1") (pintype "passive"))
      (node (ref "DS3") (pin "6") (pinfunction "com_6") (pintype "passive"))
      (node (ref "Q14") (pin "C") (pinfunction "C_C") (pintype "passive"))
    )
    (net (code "68") (name "Net-(DS4-com-Pad1)") (class "Default")
      (node (ref "DS4") (pin "1") (pinfunction "com_1") (pintype "passive"))
      (node (ref "DS4") (pin "6") (pinfunction "com_6") (pintype "passive"))
      (node (ref "Q9") (pin "C") (pinfunction "C_C") (pintype "passive"))
    )
    (net (code "69") (name "Net-(DS5-com-Pad1)") (class "Default")
      (node (ref "DS5") (pin "1") (pinfunction "com_1") (pintype "passive"))
      (node (ref "DS5") (pin "6") (pinfunction "com_6") (pintype "passive"))
      (node (ref "Q8") (pin "C") (pinfunction "C_C") (pintype "passive"))
    )
    (net (code "70") (name "Net-(DS6-com-Pad1)") (class "Default")
      (node (ref "DS6") (pin "1") (pinfunction "com_1") (pintype "passive"))
      (node (ref "DS6") (pin "6") (pinfunction "com_6") (pintype "passive"))
      (node (ref "Q7") (pin "C") (pinfunction "C_C") (pintype "passive"))
    )
    (net (code "71") (name "Net-(J3-CC1)") (class "Default")
      (node (ref "J3") (pin "A5") (pinfunction "CC1_A5") (pintype "passive"))
      (node (ref "R56") (pin "1") (pinfunction "1_1") (pintype "passive"))
    )
    (net (code "72") (name "Net-(J3-CC2)") (class "Default")
      (node (ref "J3") (pin "B5") (pinfunction "CC2_B5") (pintype "passive"))
      (node (ref "R55") (pin "2") (pinfunction "2_2") (pintype "passive"))
    )
    (net (code "73") (name "Net-(J9-Pad1)") (class "Default")
      (node (ref "J9") (pin "1") (pinfunction "1_1") (pintype "passive"))
      (node (ref "K18") (pin "NC") (pinfunction "NC_NC") (pintype "passive"))
    )
    (net (code "74") (name "Net-(J9-Pad2)") (class "Default")
      (node (ref "J9") (pin "2") (pinfunction "2_2") (pintype "passive"))
      (node (ref "K18") (pin "COM") (pinfunction "COM_COM") (pintype "passive"))
    )
    (net (code "75") (name "Net-(J9-Pad3)") (class "Default")
      (node (ref "J9") (pin "3") (pinfunction "3_3") (pintype "passive"))
      (node (ref "K18") (pin "NO") (pinfunction "NO_NO") (pintype "passive"))
    )
    (net (code "76") (name "Net-(LD1-1)") (class "Default")
      (node (ref "LD1") (pin "9") (pinfunction "1_9") (pintype "passive"))
      (node (ref "Q10") (pin "C") (pinfunction "C_C") (pintype "passive"))
    )
    (net (code "77") (name "Net-(LD1-2)") (class "Default")
      (node (ref "LD1") (pin "14") (pinfunction "2_14") (pintype "passive"))
      (node (ref "Q11") (pin "C") (pinfunction "C_C") (pintype "passive"))
    )
    (net (code "78") (name "Net-(LD1-3)") (class "Default")
      (node (ref "LD1") (pin "8") (pinfunction "3_8") (pintype "passive"))
      (node (ref "Q12") (pin "C") (pinfunction "C_C") (pintype "passive"))
    )
    (net (code "79") (name "Net-(LD1-4)") (class "Default")
      (node (ref "LD1") (pin "12") (pinfunction "4_12") (pintype "passive"))
      (node (ref "Q13") (pin "C") (pinfunction "C_C") (pintype "passive"))
    )
    (net (code "80") (name "Net-(LD1-5)") (class "Default")
      (node (ref "LD1") (pin "1") (pinfunction "5_1") (pintype "passive"))
      (node (ref "Q18") (pin "C") (pinfunction "C_C") (pintype "passive"))
    )
    (net (code "81") (name "Net-(LD1-6)") (class "Default")
      (node (ref "LD1") (pin "7") (pinfunction "6_7") (pintype "passive"))
      (node (ref "Q19") (pin "C") (pinfunction "C_C") (pintype "passive"))
    )
    (net (code "82") (name "Net-(LD1-7)") (class "Default")
      (node (ref "LD1") (pin "2") (pinfunction "7_2") (pintype "passive"))
      (node (ref "Q20") (pin "C") (pinfunction "C_C") (pintype "passive"))
    )
    (net (code "83") (name "Net-(LD1-8)") (class "Default")
      (node (ref "LD1") (pin "5") (pinfunction "8_5") (pintype "passive"))
      (node (ref "Q21") (pin "C") (pinfunction "C_C") (pintype "passive"))
    )
    (net (code "84") (name "Net-(LED1-2)") (class "Default")
      (node (ref "LED1") (pin "K") (pinfunction "2_K") (pintype "passive"))
      (node (ref "R34") (pin "1") (pinfunction "1_1") (pintype "passive"))
    )
    (net (code "85") (name "Net-(LED2-1)") (class "Default")
      (node (ref "LED2") (pin "A") (pinfunction "1_A") (pintype "passive"))
      (node (ref "LED3") (pin "A") (pinfunction "1_A") (pintype "passive"))
      (node (ref "LED4") (pin "A") (pinfunction "1_A") (pintype "passive"))
      (node (ref "LED5") (pin "A") (pinfunction "1_A") (pintype "passive"))
      (node (ref "LED6") (pin "A") (pinfunction "1_A") (pintype "passive"))
      (node (ref "LED7") (pin "A") (pinfunction "1_A") (pintype "passive"))
      (node (ref "LED8") (pin "A") (pinfunction "1_A") (pintype "passive"))
      (node (ref "LED9") (pin "A") (pinfunction "1_A") (pintype "passive"))
      (node (ref "Q16") (pin "C") (pinfunction "C_C") (pintype "passive"))
    )
    (net (code "86") (name "Net-(LED10-2)") (class "Default")
      (node (ref "LED10") (pin "K") (pinfunction "2_K") (pintype "passive"))
      (node (ref "R35") (pin "2") (pinfunction "2_2") (pintype "passive"))
    )
    (net (code "87") (name "Net-(LED11-2)") (class "Default")
      (node (ref "LED11") (pin "K") (pinfunction "2_K") (pintype "passive"))
      (node (ref "R54") (pin "2") (pinfunction "2_2") (pintype "passive"))
    )
    (net (code "88") (name "Net-(Q2-PadB)") (class "Default")
      (node (ref "Q2") (pin "B") (pinfunction "B_B") (pintype "passive"))
      (node (ref "R53") (pin "2") (pinfunction "2_2") (pintype "passive"))
    )
    (net (code "89") (name "Net-(Q7-PadB)") (class "Default")
      (node (ref "Q7") (pin "B") (pinfunction "B_B") (pintype "passive"))
      (node (ref "R37") (pin "2") (pinfunction "2_2") (pintype "passive"))
    )
    (net (code "90") (name "Net-(Q8-PadB)") (class "Default")
      (node (ref "Q8") (pin "B") (pinfunction "B_B") (pintype "passive"))
      (node (ref "R38") (pin "2") (pinfunction "2_2") (pintype "passive"))
    )
    (net (code "91") (name "Net-(Q9-PadB)") (class "Default")
      (node (ref "Q9") (pin "B") (pinfunction "B_B") (pintype "passive"))
      (node (ref "R39") (pin "2") (pinfunction "2_2") (pintype "passive"))
    )
    (net (code "92") (name "Net-(Q10-PadB)") (class "Default")
      (node (ref "Q10") (pin "B") (pinfunction "B_B") (pintype "passive"))
      (node (ref "R40") (pin "2") (pinfunction "2_2") (pintype "passive"))
    )
    (net (code "93") (name "Net-(Q11-PadB)") (class "Default")
      (node (ref "Q11") (pin "B") (pinfunction "B_B") (pintype "passive"))
      (node (ref "R41") (pin "2") (pinfunction "2_2") (pintype "passive"))
    )
    (net (code "94") (name "Net-(Q12-PadB)") (class "Default")
      (node (ref "Q12") (pin "B") (pinfunction "B_B") (pintype "passive"))
      (node (ref "R42") (pin "2") (pinfunction "2_2") (pintype "passive"))
    )
    (net (code "95") (name "Net-(Q13-PadB)") (class "Default")
      (node (ref "Q13") (pin "B") (pinfunction "B_B") (pintype "passive"))
      (node (ref "R43") (pin "2") (pinfunction "2_2") (pintype "passive"))
    )
    (net (code "96") (name "Net-(Q14-PadB)") (class "Default")
      (node (ref "Q14") (pin "B") (pinfunction "B_B") (pintype "passive"))
      (node (ref "R44") (pin "2") (pinfunction "2_2") (pintype "passive"))
    )
    (net (code "97") (name "Net-(Q15-PadB)") (class "Default")
      (node (ref "Q15") (pin "B") (pinfunction "B_B") (pintype "passive"))
      (node (ref "R45") (pin "2") (pinfunction "2_2") (pintype "passive"))
    )
    (net (code "98") (name "Net-(Q16-PadB)") (class "Default")
      (node (ref "Q16") (pin "B") (pinfunction "B_B") (pintype "passive"))
      (node (ref "R47") (pin "1") (pinfunction "1_1") (pintype "passive"))
    )
    (net (code "99") (name "Net-(Q17-PadB)") (class "Default")
      (node (ref "Q17") (pin "B") (pinfunction "B_B") (pintype "passive"))
      (node (ref "R46") (pin "2") (pinfunction "2_2") (pintype "passive"))
    )
    (net (code "100") (name "Net-(Q18-PadB)") (class "Default")
      (node (ref "Q18") (pin "B") (pinfunction "B_B") (pintype "passive"))
      (node (ref "R48") (pin "2") (pinfunction "2_2") (pintype "passive"))
    )
    (net (code "101") (name "Net-(Q19-PadB)") (class "Default")
      (node (ref "Q19") (pin "B") (pinfunction "B_B") (pintype "passive"))
      (node (ref "R49") (pin "2") (pinfunction "2_2") (pintype "passive"))
    )
    (net (code "102") (name "Net-(Q20-PadB)") (class "Default")
      (node (ref "Q20") (pin "B") (pinfunction "B_B") (pintype "passive"))
      (node (ref "R50") (pin "2") (pinfunction "2_2") (pintype "passive"))
    )
    (net (code "103") (name "Net-(Q21-PadB)") (class "Default")
      (node (ref "Q21") (pin "B") (pinfunction "B_B") (pintype "passive"))
      (node (ref "R51") (pin "2") (pinfunction "2_2") (pintype "passive"))
    )
    (net (code "104") (name "Net-(Q22-PadB)") (class "Default")
      (node (ref "Q22") (pin "B") (pinfunction "B_B") (pintype "passive"))
      (node (ref "R52") (pin "2") (pinfunction "2_2") (pintype "passive"))
    )
    (net (code "105") (name "Net-(U1-V3)") (class "Default")
      (node (ref "C3") (pin "1") (pinfunction "1_1") (pintype "passive"))
      (node (ref "U1") (pin "8") (pinfunction "V3_8") (pintype "passive"))
    )
    (net (code "106") (name "Net-(U5-XTAL1)") (class "Default")
      (node (ref "C14") (pin "1") (pinfunction "1_1") (pintype "passive"))
      (node (ref "U5") (pin "15") (pinfunction "XTAL1_15") (pintype "passive"))
      (node (ref "Y2") (pin "3") (pinfunction "3_3") (pintype "passive"))
    )
    (net (code "107") (name "Net-(U5-XTAL2)") (class "Default")
      (node (ref "C15") (pin "1") (pinfunction "1_1") (pintype "passive"))
      (node (ref "U5") (pin "14") (pinfunction "XTAL2_14") (pintype "passive"))
      (node (ref "Y2") (pin "1") (pinfunction "1_1") (pintype "passive"))
    )
    (net (code "108") (name "unconnected-(J3-SBU1-PadA8)") (class "Default")
      (node (ref "J3") (pin "A8") (pinfunction "SBU1_A8") (pintype "passive"))
    )
    (net (code "109") (name "unconnected-(J3-SBU2-PadB8)") (class "Default")
      (node (ref "J3") (pin "B8") (pinfunction "SBU2_B8") (pintype "passive"))
    )
    (net (code "110") (name "unconnected-(J3-SH-PadS1)") (class "Default")
      (node (ref "J3") (pin "S1") (pinfunction "SH_S1") (pintype "passive"))
    )
    (net (code "111") (name "unconnected-(J3-SH-PadS2)") (class "Default")
      (node (ref "J3") (pin "S2") (pinfunction "SH_S2") (pintype "passive"))
    )
    (net (code "112") (name "unconnected-(J3-SH-PadS3)") (class "Default")
      (node (ref "J3") (pin "S3") (pinfunction "SH_S3") (pintype "passive"))
    )
    (net (code "113") (name "unconnected-(J3-SH-PadS4)") (class "Default")
      (node (ref "J3") (pin "S4") (pinfunction "SH_S4") (pintype "passive"))
    )
    (net (code "114") (name "unconnected-(J10-Pad1)") (class "Default")
      (node (ref "J10") (pin "1") (pinfunction "1_1") (pintype "passive"))
    )
    (net (code "115") (name "unconnected-(J10-Pad4)") (class "Default")
      (node (ref "J10") (pin "4") (pinfunction "4_4") (pintype "passive"))
    )
    (net (code "116") (name "unconnected-(U1-RTS#-Pad4)") (class "Default")
      (node (ref "U1") (pin "4") (pinfunction "RTS#_4") (pintype "output"))
    )
    (net (code "117") (name "unconnected-(U3-~{Y7}-Pad7)") (class "Default")
      (node (ref "U3") (pin "7") (pinfunction "~{Y7}_7") (pintype "passive"))
    )
    (net (code "118") (name "unconnected-(U5-ALE-Pad27)") (class "Default")
      (node (ref "U5") (pin "27") (pinfunction "ALE_27") (pintype "passive"))
    )
    (net (code "119") (name "unconnected-(U5-P4.0-Pad17)") (class "Default")
      (node (ref "U5") (pin "17") (pinfunction "P4.0_17") (pintype "passive"))
    )
    (net (code "120") (name "unconnected-(U5-P4.1-Pad28)") (class "Default")
      (node (ref "U5") (pin "28") (pinfunction "P4.1_28") (pintype "passive"))
    )
    (net (code "121") (name "unconnected-(U5-P4.2{slash}INT3-Pad39)") (class "Default")
      (node (ref "U5") (pin "39") (pinfunction "P4.2/INT3_39") (pintype "passive"))
    )
    (net (code "122") (name "unconnected-(U5-P4.3{slash}INT2-Pad6)") (class "Default")
      (node (ref "U5") (pin "6") (pinfunction "P4.3/INT2_6") (pintype "passive"))
    )
    (net (code "123") (name "unconnected-(U5-~{PSEN}-Pad26)") (class "Default")
      (node (ref "U5") (pin "26") (pinfunction "~{PSEN}_26") (pintype "passive"))
    )
    (net (code "124") (name "unconnected-(U8-IO2-Pad3)") (class "Default")
      (node (ref "U8") (pin "3") (pinfunction "IO2_3") (pintype "bidirectional"))
    )
    (net (code "125") (name "unconnected-(U8-IO3-Pad7)") (class "Default")
      (node (ref "U8") (pin "7") (pinfunction "IO3_7") (pintype "bidirectional"))
    )
  )
)
